# Led_Board.net
KiCad netlist of a schematic drawn in EAGLE
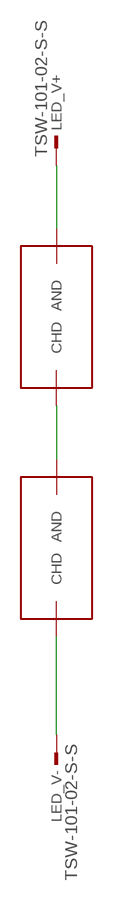
[diagram p0: schematic, sheet 1]

(export (version "E")
  (design (tool "Eeschema 10.0.6"))
  (components
    (comp (ref "LED_V+")
      (value "TSW-101-02-S-S")
      (footprint "eagle-import:TSW-101-02-S-S")
      (libsource (lib "eagle-import") (part "TSW-101-02-S-S"))
    )
    (comp (ref "LED_V-")
      (value "TSW-101-02-S-S")
      (footprint "eagle-import:TSW-101-02-S-S")
      (libsource (lib "eagle-import") (part "TSW-101-02-S-S"))
    )
    (comp (ref "U$1")
      (value "TL1F2-NW1")
      (footprint "eagle-import:TL1F2-NW1")
      (libsource (lib "eagle-import") (part "TL1F2-NW1"))
    )
    (comp (ref "U$2")
      (value "TL1F2-NW1")
      (footprint "eagle-import:TL1F2-NW1")
      (libsource (lib "eagle-import") (part "TL1F2-NW1"))
    )
  )
  (nets
    (net (code "1") (name "Net-(U$1-AND)") (class "Default")
      (node (ref "LED_V+") (pin "1") (pinfunction "1_1") (pintype "passive"))
      (node (ref "U$1") (pin "ANODE") (pinfunction "AND_ANODE") (pintype "bidirectional"))
    )
    (net (code "2") (name "Net-(U$1-CHD)") (class "Default")
      (node (ref "U$1") (pin "CATHODE") (pinfunction "CHD_CATHODE") (pintype "bidirectional"))
      (node (ref "U$2") (pin "ANODE") (pinfunction "AND_ANODE") (pintype "bidirectional"))
    )
    (net (code "3") (name "Net-(U$2-CHD)") (class "Default")
      (node (ref "LED_V-") (pin "1") (pinfunction "1_1") (pintype "passive"))
      (node (ref "U$2") (pin "CATHODE") (pinfunction "CHD_CATHODE") (pintype "bidirectional"))
    )
  )
)
